# ZynqPL_GTXE2.net
KiCad netlist of a schematic drawn in Altium Designer
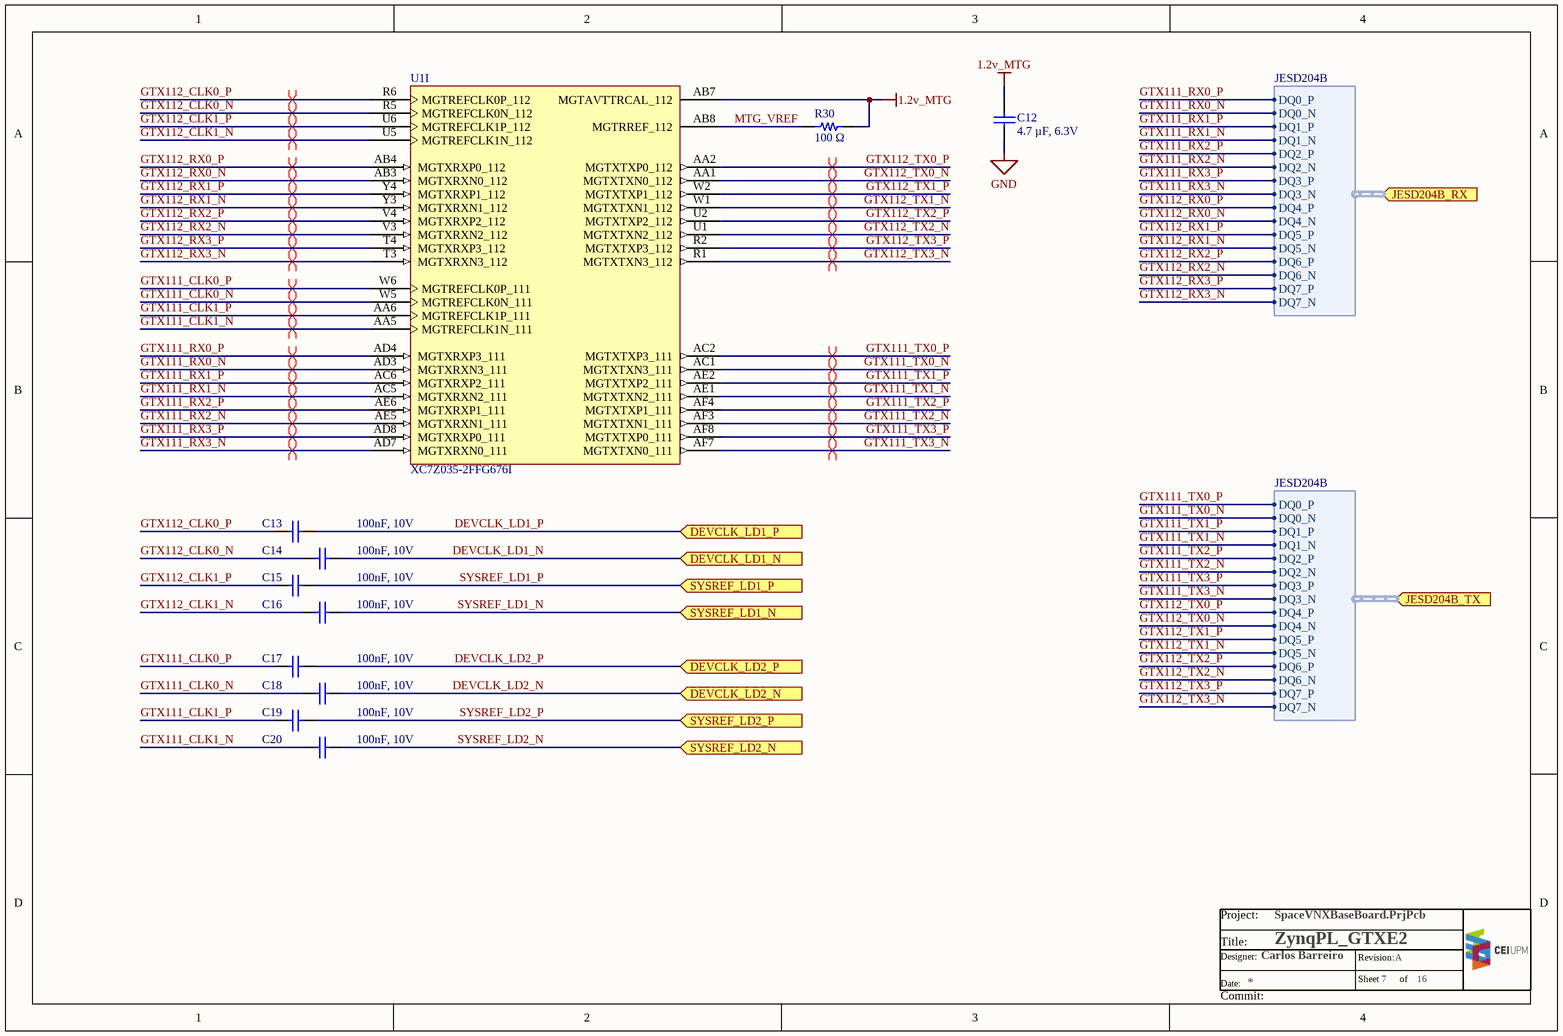
[diagram p0: ZynqPL_GTXE2.SchDoc]

(export (version "E")
  (design (tool "Eeschema 10.0.6"))
  (components
    (comp (ref "C12")
      (value "4.7 µF, 6.3V")
      (footprint "WURTH_WCAP-CSGP_0402")
      (description "Multilayer Ceramic Capacitors MLCC, size 0402, X5R, 4.7 µF, 6.3V")
      (fields
        (field (name "MANUFACTURER PART NUMBER") "GRM155C80J475MEAAD")
        (field (name "MANUFACTURER") "Murata")
      )
      (libsource (lib "SpaceVNX") (part "GRM155C80J475MEAAD"))
    )
    (comp (ref "C13")
      (value "100nF, 10V")
      (footprint "WURTH_WCAP-CSGP_0402")
      (description "WCAP-CSGP Multilayer Ceramic Chip Capacitor, General Purpose, size 0402, X7R, 100nF, 10V")
      (fields
        (field (name "MANUFACTURER PART NUMBER") "885012205018")
        (field (name "MANUFACTURER") "Wurth Elektronik")
      )
      (libsource (lib "SpaceVNX") (part "885012205018"))
    )
    (comp (ref "C14")
      (value "100nF, 10V")
      (footprint "WURTH_WCAP-CSGP_0402")
      (description "WCAP-CSGP Multilayer Ceramic Chip Capacitor, General Purpose, size 0402, X7R, 100nF, 10V")
      (fields
        (field (name "MANUFACTURER PART NUMBER") "885012205018")
        (field (name "MANUFACTURER") "Wurth Elektronik")
      )
      (libsource (lib "SpaceVNX") (part "885012205018"))
    )
    (comp (ref "C15")
      (value "100nF, 10V")
      (footprint "WURTH_WCAP-CSGP_0402")
      (description "WCAP-CSGP Multilayer Ceramic Chip Capacitor, General Purpose, size 0402, X7R, 100nF, 10V")
      (fields
        (field (name "MANUFACTURER PART NUMBER") "885012205018")
        (field (name "MANUFACTURER") "Wurth Elektronik")
      )
      (libsource (lib "SpaceVNX") (part "885012205018"))
    )
    (comp (ref "C16")
      (value "100nF, 10V")
      (footprint "WURTH_WCAP-CSGP_0402")
      (description "WCAP-CSGP Multilayer Ceramic Chip Capacitor, General Purpose, size 0402, X7R, 100nF, 10V")
      (fields
        (field (name "MANUFACTURER PART NUMBER") "885012205018")
        (field (name "MANUFACTURER") "Wurth Elektronik")
      )
      (libsource (lib "SpaceVNX") (part "885012205018"))
    )
    (comp (ref "C17")
      (value "100nF, 10V")
      (footprint "WURTH_WCAP-CSGP_0402")
      (description "WCAP-CSGP Multilayer Ceramic Chip Capacitor, General Purpose, size 0402, X7R, 100nF, 10V")
      (fields
        (field (name "MANUFACTURER PART NUMBER") "885012205018")
        (field (name "MANUFACTURER") "Wurth Elektronik")
      )
      (libsource (lib "SpaceVNX") (part "885012205018"))
    )
    (comp (ref "C18")
      (value "100nF, 10V")
      (footprint "WURTH_WCAP-CSGP_0402")
      (description "WCAP-CSGP Multilayer Ceramic Chip Capacitor, General Purpose, size 0402, X7R, 100nF, 10V")
      (fields
        (field (name "MANUFACTURER PART NUMBER") "885012205018")
        (field (name "MANUFACTURER") "Wurth Elektronik")
      )
      (libsource (lib "SpaceVNX") (part "885012205018"))
    )
    (comp (ref "C19")
      (value "100nF, 10V")
      (footprint "WURTH_WCAP-CSGP_0402")
      (description "WCAP-CSGP Multilayer Ceramic Chip Capacitor, General Purpose, size 0402, X7R, 100nF, 10V")
      (fields
        (field (name "MANUFACTURER PART NUMBER") "885012205018")
        (field (name "MANUFACTURER") "Wurth Elektronik")
      )
      (libsource (lib "SpaceVNX") (part "885012205018"))
    )
    (comp (ref "C20")
      (value "100nF, 10V")
      (footprint "WURTH_WCAP-CSGP_0402")
      (description "WCAP-CSGP Multilayer Ceramic Chip Capacitor, General Purpose, size 0402, X7R, 100nF, 10V")
      (fields
        (field (name "MANUFACTURER PART NUMBER") "885012205018")
        (field (name "MANUFACTURER") "Wurth Elektronik")
      )
      (libsource (lib "SpaceVNX") (part "885012205018"))
    )
    (comp (ref "R30")
      (value "100 Ω")
      (footprint "PANASONIC_ERJ2G_0402")
      (description "General Purpose Thick Film Chip Resistors")
      (fields (field (name "MANUFACTURER") "Panasonic"))
      (libsource (lib "SpaceVNX") (part "ERJ2GEJ101X"))
    )
    (comp (ref "U1")
      (value "XC7Z035-2FFG676I")
      (footprint "XILINX_FBG676")
      (fields (field (name "PARTNUMBER") "XC7Z035-2FBG676I") (field (name "GENERIC PART NUMBER") "XC7Z035"))
      (libsource (lib "SpaceVNX") (part "XC7Z035-2FFG676I"))
    )
  )
  (nets
    (net (code "2") (name "/DEVCLK_LD1_N") (class "Default")
      (node (ref "C14") (pin "2") (pinfunction "2_2") (pintype "passive"))
    )
    (net (code "3") (name "/DEVCLK_LD1_P") (class "Default")
      (node (ref "C13") (pin "2") (pinfunction "2_2") (pintype "passive"))
    )
    (net (code "4") (name "/DEVCLK_LD2_N") (class "Default")
      (node (ref "C18") (pin "2") (pinfunction "2_2") (pintype "passive"))
    )
    (net (code "5") (name "/DEVCLK_LD2_P") (class "Default")
      (node (ref "C17") (pin "2") (pinfunction "2_2") (pintype "passive"))
    )
    (net (code "6") (name "/GTX111_CLK0_N") (class "Default")
      (node (ref "C18") (pin "1") (pinfunction "1_1") (pintype "passive"))
      (node (ref "U1") (pin "W5") (pinfunction "MGTREFCLK0N_111_W5") (pintype "passive"))
    )
    (net (code "7") (name "/GTX111_CLK0_P") (class "Default")
      (node (ref "C17") (pin "1") (pinfunction "1_1") (pintype "passive"))
      (node (ref "U1") (pin "W6") (pinfunction "MGTREFCLK0P_111_W6") (pintype "passive"))
    )
    (net (code "8") (name "/GTX111_CLK1_N") (class "Default")
      (node (ref "C20") (pin "1") (pinfunction "1_1") (pintype "passive"))
      (node (ref "U1") (pin "AA5") (pinfunction "MGTREFCLK1N_111_AA5") (pintype "passive"))
    )
    (net (code "9") (name "/GTX111_CLK1_P") (class "Default")
      (node (ref "C19") (pin "1") (pinfunction "1_1") (pintype "passive"))
      (node (ref "U1") (pin "AA6") (pinfunction "MGTREFCLK1P_111_AA6") (pintype "passive"))
    )
    (net (code "10") (name "/GTX111_RX0_N") (class "Default")
      (node (ref "U1") (pin "AD3") (pinfunction "MGTXRXN3_111_AD3") (pintype "input"))
    )
    (net (code "11") (name "/GTX111_RX0_P") (class "Default")
      (node (ref "U1") (pin "AD4") (pinfunction "MGTXRXP3_111_AD4") (pintype "input"))
    )
    (net (code "12") (name "/GTX111_RX1_N") (class "Default")
      (node (ref "U1") (pin "AC5") (pinfunction "MGTXRXN2_111_AC5") (pintype "input"))
    )
    (net (code "13") (name "/GTX111_RX1_P") (class "Default")
      (node (ref "U1") (pin "AC6") (pinfunction "MGTXRXP2_111_AC6") (pintype "input"))
    )
    (net (code "14") (name "/GTX111_RX2_N") (class "Default")
      (node (ref "U1") (pin "AE5") (pinfunction "MGTXRXN1_111_AE5") (pintype "input"))
    )
    (net (code "15") (name "/GTX111_RX2_P") (class "Default")
      (node (ref "U1") (pin "AE6") (pinfunction "MGTXRXP1_111_AE6") (pintype "input"))
    )
    (net (code "16") (name "/GTX111_RX3_N") (class "Default")
      (node (ref "U1") (pin "AD7") (pinfunction "MGTXRXN0_111_AD7") (pintype "input"))
    )
    (net (code "17") (name "/GTX111_RX3_P") (class "Default")
      (node (ref "U1") (pin "AD8") (pinfunction "MGTXRXP0_111_AD8") (pintype "input"))
    )
    (net (code "18") (name "/GTX111_TX0_N") (class "Default")
      (node (ref "U1") (pin "AC1") (pinfunction "MGTXTXN3_111_AC1") (pintype "output"))
    )
    (net (code "19") (name "/GTX111_TX0_P") (class "Default")
      (node (ref "U1") (pin "AC2") (pinfunction "MGTXTXP3_111_AC2") (pintype "output"))
    )
    (net (code "20") (name "/GTX111_TX1_N") (class "Default")
      (node (ref "U1") (pin "AE1") (pinfunction "MGTXTXN2_111_AE1") (pintype "output"))
    )
    (net (code "21") (name "/GTX111_TX1_P") (class "Default")
      (node (ref "U1") (pin "AE2") (pinfunction "MGTXTXP2_111_AE2") (pintype "output"))
    )
    (net (code "22") (name "/GTX111_TX2_N") (class "Default")
      (node (ref "U1") (pin "AF3") (pinfunction "MGTXTXN1_111_AF3") (pintype "output"))
    )
    (net (code "23") (name "/GTX111_TX2_P") (class "Default")
      (node (ref "U1") (pin "AF4") (pinfunction "MGTXTXP1_111_AF4") (pintype "output"))
    )
    (net (code "24") (name "/GTX111_TX3_N") (class "Default")
      (node (ref "U1") (pin "AF7") (pinfunction "MGTXTXN0_111_AF7") (pintype "output"))
    )
    (net (code "25") (name "/GTX111_TX3_P") (class "Default")
      (node (ref "U1") (pin "AF8") (pinfunction "MGTXTXP0_111_AF8") (pintype "output"))
    )
    (net (code "26") (name "/GTX112_CLK0_N") (class "Default")
      (node (ref "C14") (pin "1") (pinfunction "1_1") (pintype "passive"))
      (node (ref "U1") (pin "R5") (pinfunction "MGTREFCLK0N_112_R5") (pintype "passive"))
    )
    (net (code "27") (name "/GTX112_CLK0_P") (class "Default")
      (node (ref "C13") (pin "1") (pinfunction "1_1") (pintype "passive"))
      (node (ref "U1") (pin "R6") (pinfunction "MGTREFCLK0P_112_R6") (pintype "passive"))
    )
    (net (code "28") (name "/GTX112_CLK1_N") (class "Default")
      (node (ref "C16") (pin "1") (pinfunction "1_1") (pintype "passive"))
      (node (ref "U1") (pin "U5") (pinfunction "MGTREFCLK1N_112_U5") (pintype "passive"))
    )
    (net (code "29") (name "/GTX112_CLK1_P") (class "Default")
      (node (ref "C15") (pin "1") (pinfunction "1_1") (pintype "passive"))
      (node (ref "U1") (pin "U6") (pinfunction "MGTREFCLK1P_112_U6") (pintype "passive"))
    )
    (net (code "30") (name "/GTX112_RX0_N") (class "Default")
      (node (ref "U1") (pin "AB3") (pinfunction "MGTXRXN0_112_AB3") (pintype "input"))
    )
    (net (code "31") (name "/GTX112_RX0_P") (class "Default")
      (node (ref "U1") (pin "AB4") (pinfunction "MGTXRXP0_112_AB4") (pintype "input"))
    )
    (net (code "32") (name "/GTX112_RX1_N") (class "Default")
      (node (ref "U1") (pin "Y3") (pinfunction "MGTXRXN1_112_Y3") (pintype "input"))
    )
    (net (code "33") (name "/GTX112_RX1_P") (class "Default")
      (node (ref "U1") (pin "Y4") (pinfunction "MGTXRXP1_112_Y4") (pintype "input"))
    )
    (net (code "34") (name "/GTX112_RX2_N") (class "Default")
      (node (ref "U1") (pin "V3") (pinfunction "MGTXRXN2_112_V3") (pintype "input"))
    )
    (net (code "35") (name "/GTX112_RX2_P") (class "Default")
      (node (ref "U1") (pin "V4") (pinfunction "MGTXRXP2_112_V4") (pintype "input"))
    )
    (net (code "36") (name "/GTX112_RX3_N") (class "Default")
      (node (ref "U1") (pin "T3") (pinfunction "MGTXRXN3_112_T3") (pintype "input"))
    )
    (net (code "37") (name "/GTX112_RX3_P") (class "Default")
      (node (ref "U1") (pin "T4") (pinfunction "MGTXRXP3_112_T4") (pintype "input"))
    )
    (net (code "38") (name "/GTX112_TX0_N") (class "Default")
      (node (ref "U1") (pin "AA1") (pinfunction "MGTXTXN0_112_AA1") (pintype "output"))
    )
    (net (code "39") (name "/GTX112_TX0_P") (class "Default")
      (node (ref "U1") (pin "AA2") (pinfunction "MGTXTXP0_112_AA2") (pintype "output"))
    )
    (net (code "40") (name "/GTX112_TX1_N") (class "Default")
      (node (ref "U1") (pin "W1") (pinfunction "MGTXTXN1_112_W1") (pintype "output"))
    )
    (net (code "41") (name "/GTX112_TX1_P") (class "Default")
      (node (ref "U1") (pin "W2") (pinfunction "MGTXTXP1_112_W2") (pintype "output"))
    )
    (net (code "42") (name "/GTX112_TX2_N") (class "Default")
      (node (ref "U1") (pin "U1") (pinfunction "MGTXTXN2_112_U1") (pintype "output"))
    )
    (net (code "43") (name "/GTX112_TX2_P") (class "Default")
      (node (ref "U1") (pin "U2") (pinfunction "MGTXTXP2_112_U2") (pintype "output"))
    )
    (net (code "44") (name "/GTX112_TX3_N") (class "Default")
      (node (ref "U1") (pin "R1") (pinfunction "MGTXTXN3_112_R1") (pintype "output"))
    )
    (net (code "45") (name "/GTX112_TX3_P") (class "Default")
      (node (ref "U1") (pin "R2") (pinfunction "MGTXTXP3_112_R2") (pintype "output"))
    )
    (net (code "46") (name "/MTG_VREF") (class "Default")
      (node (ref "R30") (pin "1") (pinfunction "1_1") (pintype "passive"))
      (node (ref "U1") (pin "AB8") (pinfunction "MGTRREF_112_AB8") (pintype "passive"))
    )
    (net (code "47") (name "/SYSREF_LD1_N") (class "Default")
      (node (ref "C16") (pin "2") (pinfunction "2_2") (pintype "passive"))
    )
    (net (code "48") (name "/SYSREF_LD1_P") (class "Default")
      (node (ref "C15") (pin "2") (pinfunction "2_2") (pintype "passive"))
    )
    (net (code "49") (name "/SYSREF_LD2_N") (class "Default")
      (node (ref "C20") (pin "2") (pinfunction "2_2") (pintype "passive"))
    )
    (net (code "50") (name "/SYSREF_LD2_P") (class "Default")
      (node (ref "C19") (pin "2") (pinfunction "2_2") (pintype "passive"))
    )
    (net (code "52") (name "1.2v_MTG") (class "Default")
      (node (ref "C12") (pin "2") (pinfunction "2_2") (pintype "passive"))
      (node (ref "R30") (pin "2") (pinfunction "2_2") (pintype "passive"))
      (node (ref "U1") (pin "AB7") (pinfunction "MGTAVTTRCAL_112_AB7") (pintype "passive"))
    )
    (net (code "53") (name "GND") (class "Default")
      (node (ref "C12") (pin "1") (pinfunction "1_1") (pintype "passive"))
    )
  )
)
